# AliDualVar.net
KiCad netlist of a schematic drawn in EAGLE
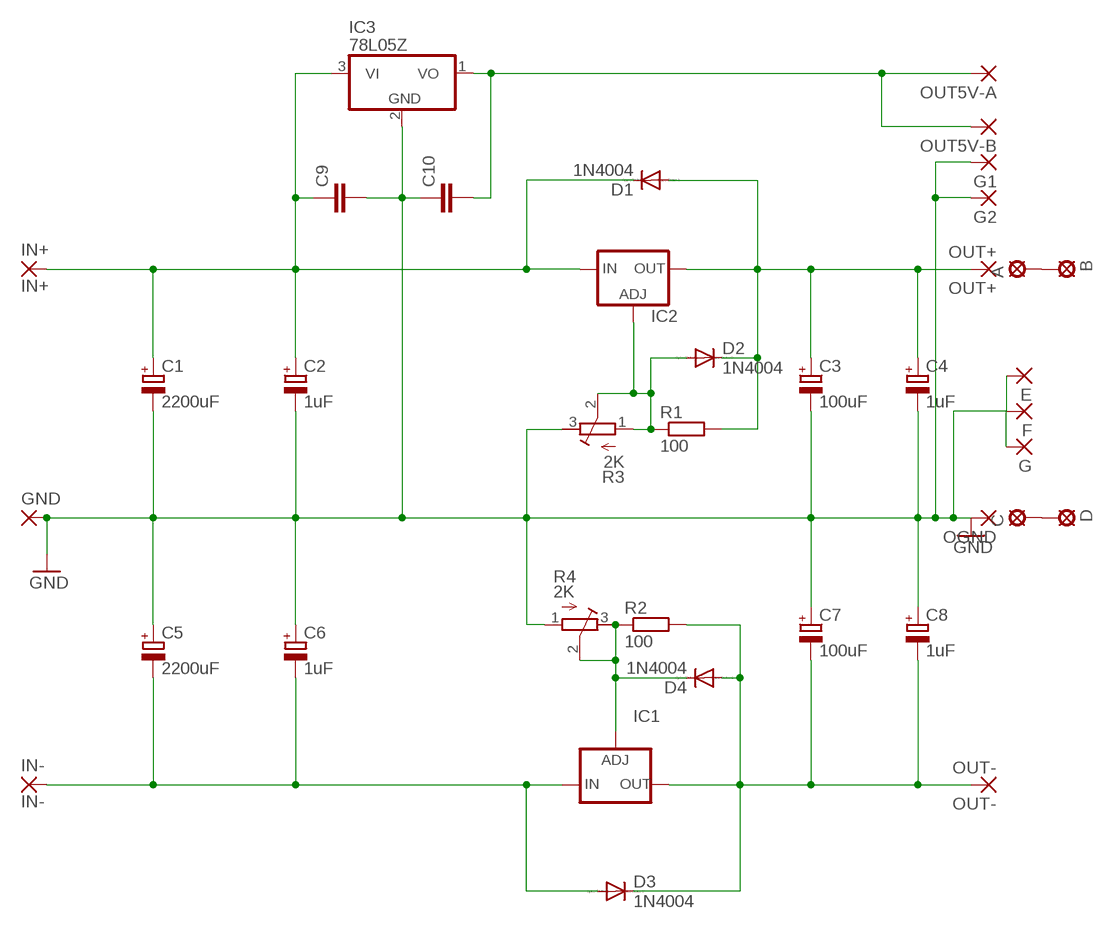
[diagram p0: schematic, sheet 1]

(export (version "E")
  (design (tool "Eeschema 10.0.6"))
  (components
    (comp (ref "A")
      (value "MCS10B")
      (footprint "eagle-import:MCS10B")
      (libsource (lib "eagle-import") (part "MCS10B"))
    )
    (comp (ref "B")
      (value "MCS10B")
      (footprint "eagle-import:MCS10B")
      (libsource (lib "eagle-import") (part "MCS10B"))
    )
    (comp (ref "C")
      (value "MCS10B")
      (footprint "eagle-import:MCS10B")
      (libsource (lib "eagle-import") (part "MCS10B"))
    )
    (comp (ref "C1")
      (value "2200uF")
      (footprint "eagle-import:EB35D")
      (libsource (lib "eagle-import") (part "CPOL-EUE10-35"))
    )
    (comp (ref "C2")
      (value "1uF")
      (footprint "eagle-import:E5-13")
      (libsource (lib "eagle-import") (part "CPOL-EUE5-13"))
    )
    (comp (ref "C3")
      (value "100uF")
      (footprint "eagle-import:E5-13")
      (libsource (lib "eagle-import") (part "CPOL-EUE5-13"))
    )
    (comp (ref "C4")
      (value "1uF")
      (footprint "eagle-import:E5-13")
      (libsource (lib "eagle-import") (part "CPOL-EUE5-13"))
    )
    (comp (ref "C5")
      (value "2200uF")
      (footprint "eagle-import:EB35D")
      (libsource (lib "eagle-import") (part "CPOL-EUE10-35"))
    )
    (comp (ref "C6")
      (value "1uF")
      (footprint "eagle-import:E5-13")
      (libsource (lib "eagle-import") (part "CPOL-EUE5-13"))
    )
    (comp (ref "C7")
      (value "100uF")
      (footprint "eagle-import:E5-13")
      (libsource (lib "eagle-import") (part "CPOL-EUE5-13"))
    )
    (comp (ref "C8")
      (value "1uF")
      (footprint "eagle-import:E5-13")
      (libsource (lib "eagle-import") (part "CPOL-EUE5-13"))
    )
    (comp (ref "C9")
      (value "C-EU025-024X044")
      (footprint "eagle-import:C025-024X044")
      (libsource (lib "eagle-import") (part "C-EU025-024X044"))
    )
    (comp (ref "C10")
      (value "C-EU025-024X044")
      (footprint "eagle-import:C025-024X044")
      (libsource (lib "eagle-import") (part "C-EU025-024X044"))
    )
    (comp (ref "D")
      (value "MCS10B")
      (footprint "eagle-import:MCS10B")
      (libsource (lib "eagle-import") (part "MCS10B"))
    )
    (comp (ref "D1")
      (value "1N4004")
      (footprint "eagle-import:DO41-10")
      (libsource (lib "eagle-import") (part "1N4004"))
    )
    (comp (ref "D2")
      (value "1N4004")
      (footprint "eagle-import:DO41-10")
      (libsource (lib "eagle-import") (part "1N4004"))
    )
    (comp (ref "D3")
      (value "1N4004")
      (footprint "eagle-import:DO41-10")
      (libsource (lib "eagle-import") (part "1N4004"))
    )
    (comp (ref "D4")
      (value "1N4004")
      (footprint "eagle-import:DO41-10")
      (libsource (lib "eagle-import") (part "1N4004"))
    )
    (comp (ref "E")
      (value "3,81/1,4")
      (footprint "eagle-import:3,81_1,4")
      (libsource (lib "eagle-import") (part "3,81/1,4"))
    )
    (comp (ref "F")
      (value "3,81/1,4")
      (footprint "eagle-import:3,81_1,4")
      (libsource (lib "eagle-import") (part "3,81/1,4"))
    )
    (comp (ref "G")
      (value "3,81/1,4")
      (footprint "eagle-import:3,81_1,4")
      (libsource (lib "eagle-import") (part "3,81/1,4"))
    )
    (comp (ref "G1")
      (value "3,81/1,4")
      (footprint "eagle-import:3,81_1,4")
      (libsource (lib "eagle-import") (part "3,81/1,4"))
    )
    (comp (ref "G2")
      (value "3,81/1,4")
      (footprint "eagle-import:3,81_1,4")
      (libsource (lib "eagle-import") (part "3,81/1,4"))
    )
    (comp (ref "GND")
      (value "3,81/1,4")
      (footprint "eagle-import:3,81_1,4")
      (libsource (lib "eagle-import") (part "3,81/1,4"))
    )
    (comp (ref "IC1")
      (value "LM337TL")
      (footprint "eagle-import:337TL")
      (libsource (lib "eagle-import") (part "LM337TL"))
    )
    (comp (ref "IC2")
      (value "LM317TL")
      (footprint "eagle-import:317TL")
      (libsource (lib "eagle-import") (part "LM317TL"))
    )
    (comp (ref "IC3")
      (value "78L05Z")
      (footprint "eagle-import:TO92")
      (libsource (lib "eagle-import") (part "78ZL05"))
    )
    (comp (ref "IN+")
      (value "IN+")
      (footprint "eagle-import:3,81_1,4")
      (libsource (lib "eagle-import") (part "3,81/1,4"))
    )
    (comp (ref "IN-")
      (value "IN-")
      (footprint "eagle-import:3,81_1,4")
      (libsource (lib "eagle-import") (part "3,81/1,4"))
    )
    (comp (ref "OGND")
      (value "3,81/1,4")
      (footprint "eagle-import:3,81_1,4")
      (libsource (lib "eagle-import") (part "3,81/1,4"))
    )
    (comp (ref "OUT+")
      (value "OUT+")
      (footprint "eagle-import:3,81_1,4")
      (libsource (lib "eagle-import") (part "3,81/1,4"))
    )
    (comp (ref "OUT-")
      (value "OUT-")
      (footprint "eagle-import:3,81_1,4")
      (libsource (lib "eagle-import") (part "3,81/1,4"))
    )
    (comp (ref "OUT5V-A")
      (value "3,81/1,4")
      (footprint "eagle-import:3,81_1,4")
      (libsource (lib "eagle-import") (part "3,81/1,4"))
    )
    (comp (ref "OUT5V-B")
      (value "3,81/1,4")
      (footprint "eagle-import:3,81_1,4")
      (libsource (lib "eagle-import") (part "3,81/1,4"))
    )
    (comp (ref "R1")
      (value "100")
      (footprint "eagle-import:0207_7")
      (libsource (lib "eagle-import") (part "R-EU_0207/7"))
    )
    (comp (ref "R2")
      (value "100")
      (footprint "eagle-import:0207_7")
      (libsource (lib "eagle-import") (part "R-EU_0207/7"))
    )
    (comp (ref "R3")
      (value "2K")
      (footprint "eagle-import:RTRIM3339P")
      (libsource (lib "eagle-import") (part "R-TRIMM3339P"))
    )
    (comp (ref "R4")
      (value "2K")
      (footprint "eagle-import:RTRIM3339P")
      (libsource (lib "eagle-import") (part "R-TRIMM3339P"))
    )
  )
  (nets
    (net (code "1") (name "GND") (class "Default")
      (node (ref "C1") (pin "-") (pinfunction "-_-") (pintype "passive"))
      (node (ref "C10") (pin "1") (pinfunction "1_1") (pintype "passive"))
      (node (ref "C2") (pin "-") (pinfunction "-_-") (pintype "passive"))
      (node (ref "C3") (pin "-") (pinfunction "-_-") (pintype "passive"))
      (node (ref "C4") (pin "-") (pinfunction "-_-") (pintype "passive"))
      (node (ref "C5") (pin "+") (pinfunction "+_+") (pintype "passive"))
      (node (ref "C6") (pin "+") (pinfunction "+_+") (pintype "passive"))
      (node (ref "C7") (pin "+") (pinfunction "+_+") (pintype "passive"))
      (node (ref "C8") (pin "+") (pinfunction "+_+") (pintype "passive"))
      (node (ref "C9") (pin "2") (pinfunction "2_2") (pintype "passive"))
      (node (ref "E") (pin "1") (pinfunction "P_1") (pintype "passive"))
      (node (ref "F") (pin "1") (pinfunction "P_1") (pintype "passive"))
      (node (ref "G") (pin "1") (pinfunction "P_1") (pintype "passive"))
      (node (ref "G1") (pin "1") (pinfunction "P_1") (pintype "passive"))
      (node (ref "G2") (pin "1") (pinfunction "P_1") (pintype "passive"))
      (node (ref "GND") (pin "1") (pinfunction "P_1") (pintype "passive"))
      (node (ref "IC3") (pin "2") (pinfunction "GND_2") (pintype "passive"))
      (node (ref "OGND") (pin "1") (pinfunction "P_1") (pintype "passive"))
      (node (ref "R3") (pin "3") (pinfunction "E_3") (pintype "passive"))
      (node (ref "R4") (pin "1") (pinfunction "A_1") (pintype "passive"))
    )
    (net (code "2") (name "Net-(A-PadMP)") (class "Default")
      (node (ref "A") (pin "MP") (pinfunction "MP_MP") (pintype "passive"))
      (node (ref "B") (pin "MP") (pinfunction "MP_MP") (pintype "passive"))
    )
    (net (code "3") (name "Net-(C-PadMP)") (class "Default")
      (node (ref "C") (pin "MP") (pinfunction "MP_MP") (pintype "passive"))
      (node (ref "D") (pin "MP") (pinfunction "MP_MP") (pintype "passive"))
    )
    (net (code "4") (name "Net-(IC1-ADJ)") (class "Default")
      (node (ref "D4") (pin "C") (pinfunction "C_C") (pintype "passive"))
      (node (ref "IC1") (pin "1") (pinfunction "ADJ_1") (pintype "input"))
      (node (ref "R2") (pin "1") (pinfunction "1_1") (pintype "passive"))
      (node (ref "R4") (pin "2") (pinfunction "S_2") (pintype "passive"))
      (node (ref "R4") (pin "3") (pinfunction "E_3") (pintype "passive"))
    )
    (net (code "5") (name "Net-(IC1-IN)") (class "Default")
      (node (ref "C5") (pin "-") (pinfunction "-_-") (pintype "passive"))
      (node (ref "C6") (pin "-") (pinfunction "-_-") (pintype "passive"))
      (node (ref "D3") (pin "A") (pinfunction "A_A") (pintype "passive"))
      (node (ref "IC1") (pin "2") (pinfunction "IN_2") (pintype "input"))
      (node (ref "IN-") (pin "1") (pinfunction "P_1") (pintype "passive"))
    )
    (net (code "6") (name "Net-(IC1-OUT)") (class "Default")
      (node (ref "C7") (pin "-") (pinfunction "-_-") (pintype "passive"))
      (node (ref "C8") (pin "-") (pinfunction "-_-") (pintype "passive"))
      (node (ref "D3") (pin "C") (pinfunction "C_C") (pintype "passive"))
      (node (ref "D4") (pin "A") (pinfunction "A_A") (pintype "passive"))
      (node (ref "IC1") (pin "3") (pinfunction "OUT_3") (pintype "passive"))
      (node (ref "OUT-") (pin "1") (pinfunction "P_1") (pintype "passive"))
      (node (ref "R2") (pin "2") (pinfunction "2_2") (pintype "passive"))
    )
    (net (code "7") (name "Net-(IC2-ADJ)") (class "Default")
      (node (ref "D2") (pin "A") (pinfunction "A_A") (pintype "passive"))
      (node (ref "IC2") (pin "1") (pinfunction "ADJ_1") (pintype "input"))
      (node (ref "R1") (pin "1") (pinfunction "1_1") (pintype "passive"))
      (node (ref "R3") (pin "1") (pinfunction "A_1") (pintype "passive"))
      (node (ref "R3") (pin "2") (pinfunction "S_2") (pintype "passive"))
    )
    (net (code "8") (name "Net-(IC2-IN)") (class "Default")
      (node (ref "C1") (pin "+") (pinfunction "+_+") (pintype "passive"))
      (node (ref "C2") (pin "+") (pinfunction "+_+") (pintype "passive"))
      (node (ref "C9") (pin "1") (pinfunction "1_1") (pintype "passive"))
      (node (ref "D1") (pin "C") (pinfunction "C_C") (pintype "passive"))
      (node (ref "IC2") (pin "3") (pinfunction "IN_3") (pintype "input"))
      (node (ref "IC3") (pin "3") (pinfunction "VI_3") (pintype "input"))
      (node (ref "IN+") (pin "1") (pinfunction "P_1") (pintype "passive"))
    )
    (net (code "9") (name "Net-(IC2-OUT)") (class "Default")
      (node (ref "C3") (pin "+") (pinfunction "+_+") (pintype "passive"))
      (node (ref "C4") (pin "+") (pinfunction "+_+") (pintype "passive"))
      (node (ref "D1") (pin "A") (pinfunction "A_A") (pintype "passive"))
      (node (ref "D2") (pin "C") (pinfunction "C_C") (pintype "passive"))
      (node (ref "IC2") (pin "2") (pinfunction "OUT_2") (pintype "passive"))
      (node (ref "OUT+") (pin "1") (pinfunction "P_1") (pintype "passive"))
      (node (ref "R1") (pin "2") (pinfunction "2_2") (pintype "passive"))
    )
    (net (code "10") (name "Net-(IC3-VO)") (class "Default")
      (node (ref "C10") (pin "2") (pinfunction "2_2") (pintype "passive"))
      (node (ref "IC3") (pin "1") (pinfunction "VO_1") (pintype "passive"))
      (node (ref "OUT5V-A") (pin "1") (pinfunction "P_1") (pintype "passive"))
      (node (ref "OUT5V-B") (pin "1") (pinfunction "P_1") (pintype "passive"))
    )
  )
)
